# LPCB234_-_CORE_INTERFACE.net
KiCad netlist of a schematic drawn in Altium Designer
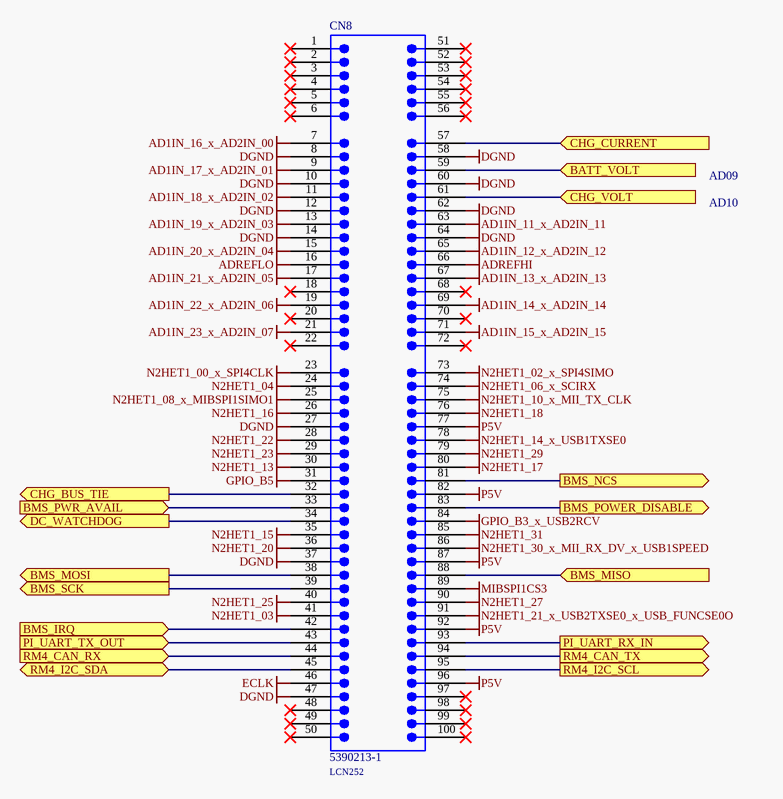
[diagram p0: LPCB234 - CORE INTERFACE.SchDoc]

(export (version "E")
  (design (tool "Eeschema 10.0.6"))
  (components
    (comp (ref "CN8")
      (value "5390213-1")
      (footprint "5390213-1")
      (description "Connector, DIMM 100")
      (fields (field (name "LDL_NUMBER") "LCN252"))
      (libsource (lib "LDL_Connectors") (part "5390213-1"))
    )
  )
  (nets
    (net (code "1") (name "/BATT_VOLT") (class "Default")
      (node (ref "CN8") (pin "59") (pinfunction "59_59") (pintype "passive"))
    )
    (net (code "2") (name "/BMS_IRQ") (class "Default")
      (node (ref "CN8") (pin "42") (pinfunction "42_42") (pintype "passive"))
    )
    (net (code "3") (name "/BMS_MISO") (class "Default")
      (node (ref "CN8") (pin "88") (pinfunction "88_88") (pintype "passive"))
    )
    (net (code "4") (name "/BMS_MOSI") (class "Default")
      (node (ref "CN8") (pin "38") (pinfunction "38_38") (pintype "passive"))
    )
    (net (code "5") (name "/BMS_NCS") (class "Default")
      (node (ref "CN8") (pin "81") (pinfunction "81_81") (pintype "passive"))
    )
    (net (code "6") (name "/BMS_POWER_DISABLE") (class "Default")
      (node (ref "CN8") (pin "83") (pinfunction "83_83") (pintype "passive"))
    )
    (net (code "7") (name "/BMS_PWR_AVAIL") (class "Default")
      (node (ref "CN8") (pin "33") (pinfunction "33_33") (pintype "passive"))
    )
    (net (code "8") (name "/BMS_SCK") (class "Default")
      (node (ref "CN8") (pin "39") (pinfunction "39_39") (pintype "passive"))
    )
    (net (code "9") (name "/CHG_BUS_TIE") (class "Default")
      (node (ref "CN8") (pin "32") (pinfunction "32_32") (pintype "passive"))
    )
    (net (code "10") (name "/CHG_CURRENT") (class "Default")
      (node (ref "CN8") (pin "57") (pinfunction "57_57") (pintype "passive"))
    )
    (net (code "11") (name "/CHG_VOLT") (class "Default")
      (node (ref "CN8") (pin "61") (pinfunction "61_61") (pintype "passive"))
    )
    (net (code "12") (name "/DC_WATCHDOG") (class "Default")
      (node (ref "CN8") (pin "34") (pinfunction "34_34") (pintype "passive"))
    )
    (net (code "13") (name "/PI_UART_RX_IN") (class "Default")
      (node (ref "CN8") (pin "93") (pinfunction "93_93") (pintype "passive"))
    )
    (net (code "14") (name "/PI_UART_TX_OUT") (class "Default")
      (node (ref "CN8") (pin "43") (pinfunction "43_43") (pintype "passive"))
    )
    (net (code "15") (name "/RM4_CAN_RX") (class "Default")
      (node (ref "CN8") (pin "44") (pinfunction "44_44") (pintype "passive"))
    )
    (net (code "16") (name "/RM4_CAN_TX") (class "Default")
      (node (ref "CN8") (pin "94") (pinfunction "94_94") (pintype "passive"))
    )
    (net (code "17") (name "/RM4_I2C_SCL") (class "Default")
      (node (ref "CN8") (pin "95") (pinfunction "95_95") (pintype "passive"))
    )
    (net (code "18") (name "/RM4_I2C_SDA") (class "Default")
      (node (ref "CN8") (pin "45") (pinfunction "45_45") (pintype "passive"))
    )
    (net (code "19") (name "AD1IN_11_x_AD2IN_11") (class "Default")
      (node (ref "CN8") (pin "63") (pinfunction "63_63") (pintype "passive"))
    )
    (net (code "20") (name "AD1IN_12_x_AD2IN_12") (class "Default")
      (node (ref "CN8") (pin "65") (pinfunction "65_65") (pintype "passive"))
    )
    (net (code "21") (name "AD1IN_13_x_AD2IN_13") (class "Default")
      (node (ref "CN8") (pin "67") (pinfunction "67_67") (pintype "passive"))
    )
    (net (code "22") (name "AD1IN_14_x_AD2IN_14") (class "Default")
      (node (ref "CN8") (pin "69") (pinfunction "69_69") (pintype "passive"))
    )
    (net (code "23") (name "AD1IN_15_x_AD2IN_15") (class "Default")
      (node (ref "CN8") (pin "71") (pinfunction "71_71") (pintype "passive"))
    )
    (net (code "24") (name "AD1IN_16_x_AD2IN_00") (class "Default")
      (node (ref "CN8") (pin "7") (pinfunction "7_7") (pintype "passive"))
    )
    (net (code "25") (name "AD1IN_17_x_AD2IN_01") (class "Default")
      (node (ref "CN8") (pin "9") (pinfunction "9_9") (pintype "passive"))
    )
    (net (code "26") (name "AD1IN_18_x_AD2IN_02") (class "Default")
      (node (ref "CN8") (pin "11") (pinfunction "11_11") (pintype "passive"))
    )
    (net (code "27") (name "AD1IN_19_x_AD2IN_03") (class "Default")
      (node (ref "CN8") (pin "13") (pinfunction "13_13") (pintype "passive"))
    )
    (net (code "28") (name "AD1IN_20_x_AD2IN_04") (class "Default")
      (node (ref "CN8") (pin "15") (pinfunction "15_15") (pintype "passive"))
    )
    (net (code "29") (name "AD1IN_21_x_AD2IN_05") (class "Default")
      (node (ref "CN8") (pin "17") (pinfunction "17_17") (pintype "passive"))
    )
    (net (code "30") (name "AD1IN_22_x_AD2IN_06") (class "Default")
      (node (ref "CN8") (pin "19") (pinfunction "19_19") (pintype "passive"))
    )
    (net (code "31") (name "AD1IN_23_x_AD2IN_07") (class "Default")
      (node (ref "CN8") (pin "21") (pinfunction "21_21") (pintype "passive"))
    )
    (net (code "32") (name "ADREFHI") (class "Default")
      (node (ref "CN8") (pin "66") (pinfunction "66_66") (pintype "passive"))
    )
    (net (code "33") (name "ADREFLO") (class "Default")
      (node (ref "CN8") (pin "16") (pinfunction "16_16") (pintype "passive"))
    )
    (net (code "34") (name "DGND") (class "Default")
      (node (ref "CN8") (pin "10") (pinfunction "10_10") (pintype "passive"))
      (node (ref "CN8") (pin "12") (pinfunction "12_12") (pintype "passive"))
      (node (ref "CN8") (pin "14") (pinfunction "14_14") (pintype "passive"))
      (node (ref "CN8") (pin "27") (pinfunction "27_27") (pintype "passive"))
      (node (ref "CN8") (pin "37") (pinfunction "37_37") (pintype "passive"))
      (node (ref "CN8") (pin "47") (pinfunction "47_47") (pintype "passive"))
      (node (ref "CN8") (pin "58") (pinfunction "58_58") (pintype "passive"))
      (node (ref "CN8") (pin "60") (pinfunction "60_60") (pintype "passive"))
      (node (ref "CN8") (pin "62") (pinfunction "62_62") (pintype "passive"))
      (node (ref "CN8") (pin "64") (pinfunction "64_64") (pintype "passive"))
      (node (ref "CN8") (pin "8") (pinfunction "8_8") (pintype "passive"))
    )
    (net (code "35") (name "ECLK") (class "Default")
      (node (ref "CN8") (pin "46") (pinfunction "46_46") (pintype "passive"))
    )
    (net (code "36") (name "GPIO_B3_x_USB2RCV") (class "Default")
      (node (ref "CN8") (pin "84") (pinfunction "84_84") (pintype "passive"))
    )
    (net (code "37") (name "GPIO_B5") (class "Default")
      (node (ref "CN8") (pin "31") (pinfunction "31_31") (pintype "passive"))
    )
    (net (code "38") (name "MIBSPI1CS3") (class "Default")
      (node (ref "CN8") (pin "89") (pinfunction "89_89") (pintype "passive"))
    )
    (net (code "39") (name "N2HET1_00_x_SPI4CLK") (class "Default")
      (node (ref "CN8") (pin "23") (pinfunction "23_23") (pintype "passive"))
    )
    (net (code "40") (name "N2HET1_02_x_SPI4SIMO") (class "Default")
      (node (ref "CN8") (pin "73") (pinfunction "73_73") (pintype "passive"))
    )
    (net (code "41") (name "N2HET1_03") (class "Default")
      (node (ref "CN8") (pin "41") (pinfunction "41_41") (pintype "passive"))
    )
    (net (code "42") (name "N2HET1_04") (class "Default")
      (node (ref "CN8") (pin "24") (pinfunction "24_24") (pintype "passive"))
    )
    (net (code "43") (name "N2HET1_06_x_SCIRX") (class "Default")
      (node (ref "CN8") (pin "74") (pinfunction "74_74") (pintype "passive"))
    )
    (net (code "44") (name "N2HET1_08_x_MIBSPI1SIMO1") (class "Default")
      (node (ref "CN8") (pin "25") (pinfunction "25_25") (pintype "passive"))
    )
    (net (code "45") (name "N2HET1_10_x_MII_TX_CLK") (class "Default")
      (node (ref "CN8") (pin "75") (pinfunction "75_75") (pintype "passive"))
    )
    (net (code "46") (name "N2HET1_13") (class "Default")
      (node (ref "CN8") (pin "30") (pinfunction "30_30") (pintype "passive"))
    )
    (net (code "47") (name "N2HET1_14_x_USB1TXSE0") (class "Default")
      (node (ref "CN8") (pin "78") (pinfunction "78_78") (pintype "passive"))
    )
    (net (code "48") (name "N2HET1_15") (class "Default")
      (node (ref "CN8") (pin "35") (pinfunction "35_35") (pintype "passive"))
    )
    (net (code "49") (name "N2HET1_16") (class "Default")
      (node (ref "CN8") (pin "26") (pinfunction "26_26") (pintype "passive"))
    )
    (net (code "50") (name "N2HET1_17") (class "Default")
      (node (ref "CN8") (pin "80") (pinfunction "80_80") (pintype "passive"))
    )
    (net (code "51") (name "N2HET1_18") (class "Default")
      (node (ref "CN8") (pin "76") (pinfunction "76_76") (pintype "passive"))
    )
    (net (code "52") (name "N2HET1_20") (class "Default")
      (node (ref "CN8") (pin "36") (pinfunction "36_36") (pintype "passive"))
    )
    (net (code "53") (name "N2HET1_21_x_USB2TXSE0_x_USB_FUNCSE0O") (class "Default")
      (node (ref "CN8") (pin "91") (pinfunction "91_91") (pintype "passive"))
    )
    (net (code "54") (name "N2HET1_22") (class "Default")
      (node (ref "CN8") (pin "28") (pinfunction "28_28") (pintype "passive"))
    )
    (net (code "55") (name "N2HET1_23") (class "Default")
      (node (ref "CN8") (pin "29") (pinfunction "29_29") (pintype "passive"))
    )
    (net (code "56") (name "N2HET1_25") (class "Default")
      (node (ref "CN8") (pin "40") (pinfunction "40_40") (pintype "passive"))
    )
    (net (code "57") (name "N2HET1_27") (class "Default")
      (node (ref "CN8") (pin "90") (pinfunction "90_90") (pintype "passive"))
    )
    (net (code "58") (name "N2HET1_29") (class "Default")
      (node (ref "CN8") (pin "79") (pinfunction "79_79") (pintype "passive"))
    )
    (net (code "59") (name "N2HET1_30_x_MII_RX_DV_x_USB1SPEED") (class "Default")
      (node (ref "CN8") (pin "86") (pinfunction "86_86") (pintype "passive"))
    )
    (net (code "60") (name "N2HET1_31") (class "Default")
      (node (ref "CN8") (pin "85") (pinfunction "85_85") (pintype "passive"))
    )
    (net (code "61") (name "P5V") (class "Default")
      (node (ref "CN8") (pin "77") (pinfunction "77_77") (pintype "passive"))
      (node (ref "CN8") (pin "82") (pinfunction "82_82") (pintype "passive"))
      (node (ref "CN8") (pin "87") (pinfunction "87_87") (pintype "passive"))
      (node (ref "CN8") (pin "92") (pinfunction "92_92") (pintype "passive"))
      (node (ref "CN8") (pin "96") (pinfunction "96_96") (pintype "passive"))
    )
    (net (code "62") (name "unconnected-(CN8-Pad1)") (class "Default")
      (node (ref "CN8") (pin "1") (pinfunction "1_1") (pintype "passive+no_connect"))
    )
    (net (code "63") (name "unconnected-(CN8-Pad2)") (class "Default")
      (node (ref "CN8") (pin "2") (pinfunction "2_2") (pintype "passive+no_connect"))
    )
    (net (code "64") (name "unconnected-(CN8-Pad3)") (class "Default")
      (node (ref "CN8") (pin "3") (pinfunction "3_3") (pintype "passive+no_connect"))
    )
    (net (code "65") (name "unconnected-(CN8-Pad4)") (class "Default")
      (node (ref "CN8") (pin "4") (pinfunction "4_4") (pintype "passive+no_connect"))
    )
    (net (code "66") (name "unconnected-(CN8-Pad5)") (class "Default")
      (node (ref "CN8") (pin "5") (pinfunction "5_5") (pintype "passive+no_connect"))
    )
    (net (code "67") (name "unconnected-(CN8-Pad6)") (class "Default")
      (node (ref "CN8") (pin "6") (pinfunction "6_6") (pintype "passive+no_connect"))
    )
    (net (code "68") (name "unconnected-(CN8-Pad18)") (class "Default")
      (node (ref "CN8") (pin "18") (pinfunction "18_18") (pintype "passive+no_connect"))
    )
    (net (code "69") (name "unconnected-(CN8-Pad20)") (class "Default")
      (node (ref "CN8") (pin "20") (pinfunction "20_20") (pintype "passive+no_connect"))
    )
    (net (code "70") (name "unconnected-(CN8-Pad22)") (class "Default")
      (node (ref "CN8") (pin "22") (pinfunction "22_22") (pintype "passive+no_connect"))
    )
    (net (code "71") (name "unconnected-(CN8-Pad48)") (class "Default")
      (node (ref "CN8") (pin "48") (pinfunction "48_48") (pintype "passive+no_connect"))
    )
    (net (code "72") (name "unconnected-(CN8-Pad49)") (class "Default")
      (node (ref "CN8") (pin "49") (pinfunction "49_49") (pintype "passive+no_connect"))
    )
    (net (code "73") (name "unconnected-(CN8-Pad50)") (class "Default")
      (node (ref "CN8") (pin "50") (pinfunction "50_50") (pintype "passive+no_connect"))
    )
    (net (code "74") (name "unconnected-(CN8-Pad51)") (class "Default")
      (node (ref "CN8") (pin "51") (pinfunction "51_51") (pintype "passive+no_connect"))
    )
    (net (code "75") (name "unconnected-(CN8-Pad52)") (class "Default")
      (node (ref "CN8") (pin "52") (pinfunction "52_52") (pintype "passive+no_connect"))
    )
    (net (code "76") (name "unconnected-(CN8-Pad53)") (class "Default")
      (node (ref "CN8") (pin "53") (pinfunction "53_53") (pintype "passive+no_connect"))
    )
    (net (code "77") (name "unconnected-(CN8-Pad54)") (class "Default")
      (node (ref "CN8") (pin "54") (pinfunction "54_54") (pintype "passive+no_connect"))
    )
    (net (code "78") (name "unconnected-(CN8-Pad55)") (class "Default")
      (node (ref "CN8") (pin "55") (pinfunction "55_55") (pintype "passive+no_connect"))
    )
    (net (code "79") (name "unconnected-(CN8-Pad56)") (class "Default")
      (node (ref "CN8") (pin "56") (pinfunction "56_56") (pintype "passive+no_connect"))
    )
    (net (code "80") (name "unconnected-(CN8-Pad68)") (class "Default")
      (node (ref "CN8") (pin "68") (pinfunction "68_68") (pintype "passive+no_connect"))
    )
    (net (code "81") (name "unconnected-(CN8-Pad70)") (class "Default")
      (node (ref "CN8") (pin "70") (pinfunction "70_70") (pintype "passive+no_connect"))
    )
    (net (code "82") (name "unconnected-(CN8-Pad72)") (class "Default")
      (node (ref "CN8") (pin "72") (pinfunction "72_72") (pintype "passive+no_connect"))
    )
    (net (code "83") (name "unconnected-(CN8-Pad97)") (class "Default")
      (node (ref "CN8") (pin "97") (pinfunction "97_97") (pintype "passive+no_connect"))
    )
    (net (code "84") (name "unconnected-(CN8-Pad98)") (class "Default")
      (node (ref "CN8") (pin "98") (pinfunction "98_98") (pintype "passive+no_connect"))
    )
    (net (code "85") (name "unconnected-(CN8-Pad99)") (class "Default")
      (node (ref "CN8") (pin "99") (pinfunction "99_99") (pintype "passive+no_connect"))
    )
    (net (code "86") (name "unconnected-(CN8-Pad100)") (class "Default")
      (node (ref "CN8") (pin "100") (pinfunction "100_100") (pintype "passive+no_connect"))
    )
  )
)
